# Connectors2.net
KiCad netlist of a schematic drawn in Altium Designer
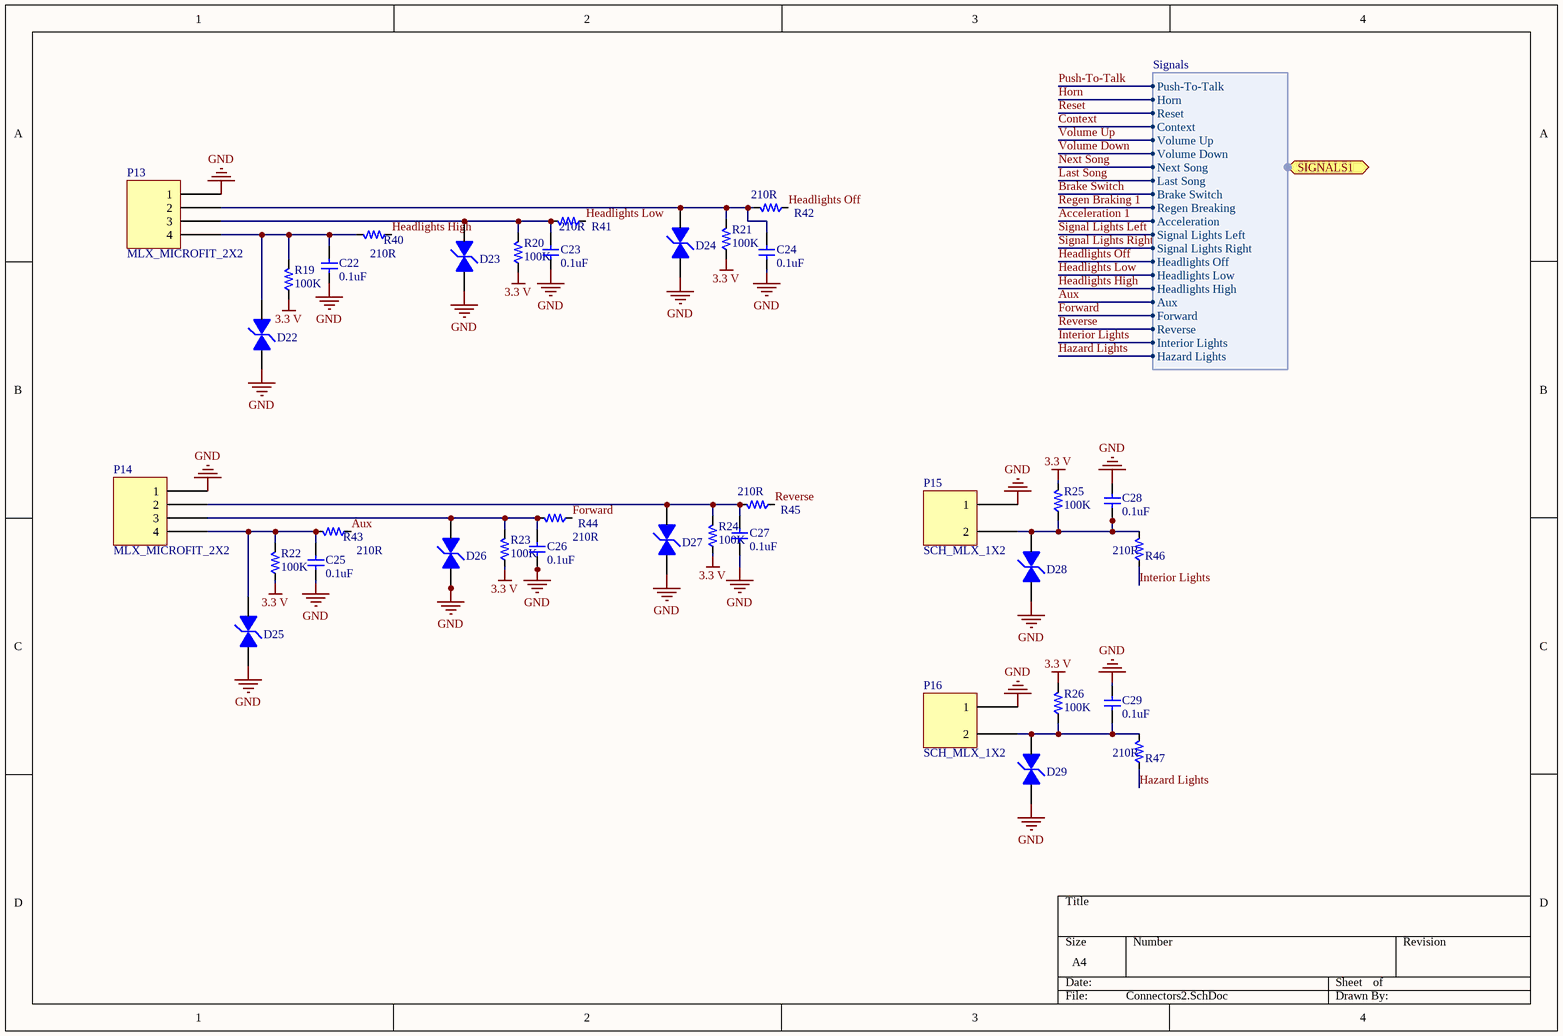
[diagram p0: Connectors2.SchDoc]

(export (version "E")
  (design (tool "Eeschema 10.0.6"))
  (components
    (comp (ref "C22")
      (value "0.1uF")
      (footprint "PCB_GENERIC_SMD_0603")
      (description "CAP CER 0603 0.1uF 16V X5R 20%")
      (fields (field (name "TOLERANCE") "20%") (field (name "VOLTAGE") "16V"))
      (libsource (lib "CAP-0603") (part "C060-000U1-00"))
    )
    (comp (ref "C23")
      (value "0.1uF")
      (footprint "PCB_GENERIC_SMD_0603")
      (description "CAP CER 0603 0.1uF 16V X5R 20%")
      (fields (field (name "TOLERANCE") "20%") (field (name "VOLTAGE") "16V"))
      (libsource (lib "CAP-0603") (part "C060-000U1-00"))
    )
    (comp (ref "C24")
      (value "0.1uF")
      (footprint "PCB_GENERIC_SMD_0603")
      (description "CAP CER 0603 0.1uF 16V X5R 20%")
      (fields (field (name "TOLERANCE") "20%") (field (name "VOLTAGE") "16V"))
      (libsource (lib "CAP-0603") (part "C060-000U1-00"))
    )
    (comp (ref "C25")
      (value "0.1uF")
      (footprint "PCB_GENERIC_SMD_0603")
      (description "CAP CER 0603 0.1uF 16V X5R 20%")
      (fields (field (name "TOLERANCE") "20%") (field (name "VOLTAGE") "16V"))
      (libsource (lib "CAP-0603") (part "C060-000U1-00"))
    )
    (comp (ref "C26")
      (value "0.1uF")
      (footprint "PCB_GENERIC_SMD_0603")
      (description "CAP CER 0603 0.1uF 16V X5R 20%")
      (fields (field (name "TOLERANCE") "20%") (field (name "VOLTAGE") "16V"))
      (libsource (lib "CAP-0603") (part "C060-000U1-00"))
    )
    (comp (ref "C27")
      (value "0.1uF")
      (footprint "PCB_GENERIC_SMD_0603")
      (description "CAP CER 0603 0.1uF 16V X5R 20%")
      (fields (field (name "TOLERANCE") "20%") (field (name "VOLTAGE") "16V"))
      (libsource (lib "CAP-0603") (part "C060-000U1-00"))
    )
    (comp (ref "C28")
      (value "0.1uF")
      (footprint "PCB_GENERIC_SMD_0603")
      (description "CAP CER 0603 0.1uF 16V X5R 20%")
      (fields (field (name "TOLERANCE") "20%") (field (name "VOLTAGE") "16V"))
      (libsource (lib "CAP-0603") (part "C060-000U1-00"))
    )
    (comp (ref "C29")
      (value "0.1uF")
      (footprint "PCB_GENERIC_SMD_0603")
      (description "CAP CER 0603 0.1uF 16V X5R 20%")
      (fields (field (name "TOLERANCE") "20%") (field (name "VOLTAGE") "16V"))
      (libsource (lib "CAP-0603") (part "C060-000U1-00"))
    )
    (comp (ref "D22")
      (value "TVS Diode")
      (footprint "TVS Diode")
      (fields (field (name "MANUFACTURER") "Bourns"))
      (libsource (lib "TVS Diode") (part "TVS Diode"))
    )
    (comp (ref "D23")
      (value "TVS Diode")
      (footprint "TVS Diode")
      (fields (field (name "MANUFACTURER") "Bourns"))
      (libsource (lib "TVS Diode") (part "TVS Diode"))
    )
    (comp (ref "D24")
      (value "TVS Diode")
      (footprint "TVS Diode")
      (fields (field (name "MANUFACTURER") "Bourns"))
      (libsource (lib "TVS Diode") (part "TVS Diode"))
    )
    (comp (ref "D25")
      (value "TVS Diode")
      (footprint "TVS Diode")
      (fields (field (name "MANUFACTURER") "Bourns"))
      (libsource (lib "TVS Diode") (part "TVS Diode"))
    )
    (comp (ref "D26")
      (value "TVS Diode")
      (footprint "TVS Diode")
      (fields (field (name "MANUFACTURER") "Bourns"))
      (libsource (lib "TVS Diode") (part "TVS Diode"))
    )
    (comp (ref "D27")
      (value "TVS Diode")
      (footprint "TVS Diode")
      (fields (field (name "MANUFACTURER") "Bourns"))
      (libsource (lib "TVS Diode") (part "TVS Diode"))
    )
    (comp (ref "D28")
      (value "TVS Diode")
      (footprint "TVS Diode")
      (fields (field (name "MANUFACTURER") "Bourns"))
      (libsource (lib "TVS Diode") (part "TVS Diode"))
    )
    (comp (ref "D29")
      (value "TVS Diode")
      (footprint "TVS Diode")
      (fields (field (name "MANUFACTURER") "Bourns"))
      (libsource (lib "TVS Diode") (part "TVS Diode"))
    )
    (comp (ref "P13")
      (value "MLX_MICROFIT_2X2")
      (footprint "MLX_MICROFIT_2X2")
      (libsource (lib "Molex Microfit 3.0 2x2") (part "MLX_MICROFIT_2X2"))
    )
    (comp (ref "P14")
      (value "MLX_MICROFIT_2X2")
      (footprint "MLX_MICROFIT_2X2")
      (libsource (lib "Molex Microfit 3.0 2x2") (part "MLX_MICROFIT_2X2"))
    )
    (comp (ref "P15")
      (value "SCH_MLX_1X2")
      (footprint "PCB_MLX_MICROFIT_1X2")
      (libsource (lib "Molex Microfit 3.0 1x2") (part "SCH_MLX_1X2"))
    )
    (comp (ref "P16")
      (value "SCH_MLX_1X2")
      (footprint "PCB_MLX_MICROFIT_1X2")
      (libsource (lib "Molex Microfit 3.0 1x2") (part "SCH_MLX_1X2"))
    )
    (comp (ref "R19")
      (value "100K")
      (footprint "PCB_GENERIC_SMD_0603")
      (description "RES 0603 100K 5% 63mW")
      (fields (field (name "TOLERANCE") "5%") (field (name "POWER") "63mW"))
      (libsource (lib "RES-0603") (part "R060-00104-05"))
    )
    (comp (ref "R20")
      (value "100K")
      (footprint "PCB_GENERIC_SMD_0603")
      (description "RES 0603 100K 5% 63mW")
      (fields (field (name "TOLERANCE") "5%") (field (name "POWER") "63mW"))
      (libsource (lib "RES-0603") (part "R060-00104-05"))
    )
    (comp (ref "R21")
      (value "100K")
      (footprint "PCB_GENERIC_SMD_0603")
      (description "RES 0603 100K 5% 63mW")
      (fields (field (name "TOLERANCE") "5%") (field (name "POWER") "63mW"))
      (libsource (lib "RES-0603") (part "R060-00104-05"))
    )
    (comp (ref "R22")
      (value "100K")
      (footprint "PCB_GENERIC_SMD_0603")
      (description "RES 0603 100K 5% 63mW")
      (fields (field (name "TOLERANCE") "5%") (field (name "POWER") "63mW"))
      (libsource (lib "RES-0603") (part "R060-00104-05"))
    )
    (comp (ref "R23")
      (value "100K")
      (footprint "PCB_GENERIC_SMD_0603")
      (description "RES 0603 100K 5% 63mW")
      (fields (field (name "TOLERANCE") "5%") (field (name "POWER") "63mW"))
      (libsource (lib "RES-0603") (part "R060-00104-05"))
    )
    (comp (ref "R24")
      (value "100K")
      (footprint "PCB_GENERIC_SMD_0603")
      (description "RES 0603 100K 5% 63mW")
      (fields (field (name "TOLERANCE") "5%") (field (name "POWER") "63mW"))
      (libsource (lib "RES-0603") (part "R060-00104-05"))
    )
    (comp (ref "R25")
      (value "100K")
      (footprint "PCB_GENERIC_SMD_0603")
      (description "RES 0603 100K 5% 63mW")
      (fields (field (name "TOLERANCE") "5%") (field (name "POWER") "63mW"))
      (libsource (lib "RES-0603") (part "R060-00104-05"))
    )
    (comp (ref "R26")
      (value "100K")
      (footprint "PCB_GENERIC_SMD_0603")
      (description "RES 0603 100K 5% 63mW")
      (fields (field (name "TOLERANCE") "5%") (field (name "POWER") "63mW"))
      (libsource (lib "RES-0603") (part "R060-00104-05"))
    )
    (comp (ref "R40")
      (value "SCH_GENERIC_RESISTOR_0603")
      (footprint "PCB_GENERIC_SMD_0603")
      (description "Generic SMD resistor 0603")
      (fields (field (name "RESISTANCE") "210R"))
      (libsource (lib "Generic 0603 Resistor") (part "SCH_GENERIC_RESISTOR_0603"))
    )
    (comp (ref "R41")
      (value "SCH_GENERIC_RESISTOR_0603")
      (footprint "PCB_GENERIC_SMD_0603")
      (description "Generic SMD resistor 0603")
      (fields (field (name "RESISTANCE") "210R"))
      (libsource (lib "Generic 0603 Resistor") (part "SCH_GENERIC_RESISTOR_0603"))
    )
    (comp (ref "R42")
      (value "SCH_GENERIC_RESISTOR_0603")
      (footprint "PCB_GENERIC_SMD_0603")
      (description "Generic SMD resistor 0603")
      (fields (field (name "RESISTANCE") "210R"))
      (libsource (lib "Generic 0603 Resistor") (part "SCH_GENERIC_RESISTOR_0603"))
    )
    (comp (ref "R43")
      (value "SCH_GENERIC_RESISTOR_0603")
      (footprint "PCB_GENERIC_SMD_0603")
      (description "Generic SMD resistor 0603")
      (fields (field (name "RESISTANCE") "210R"))
      (libsource (lib "Generic 0603 Resistor") (part "SCH_GENERIC_RESISTOR_0603"))
    )
    (comp (ref "R44")
      (value "SCH_GENERIC_RESISTOR_0603")
      (footprint "PCB_GENERIC_SMD_0603")
      (description "Generic SMD resistor 0603")
      (fields (field (name "RESISTANCE") "210R"))
      (libsource (lib "Generic 0603 Resistor") (part "SCH_GENERIC_RESISTOR_0603"))
    )
    (comp (ref "R45")
      (value "SCH_GENERIC_RESISTOR_0603")
      (footprint "PCB_GENERIC_SMD_0603")
      (description "Generic SMD resistor 0603")
      (fields (field (name "RESISTANCE") "210R"))
      (libsource (lib "Generic 0603 Resistor") (part "SCH_GENERIC_RESISTOR_0603"))
    )
    (comp (ref "R46")
      (value "SCH_GENERIC_RESISTOR_0603")
      (footprint "PCB_GENERIC_SMD_0603")
      (description "Generic SMD resistor 0603")
      (fields (field (name "RESISTANCE") "210R"))
      (libsource (lib "Generic 0603 Resistor") (part "SCH_GENERIC_RESISTOR_0603"))
    )
    (comp (ref "R47")
      (value "SCH_GENERIC_RESISTOR_0603")
      (footprint "PCB_GENERIC_SMD_0603")
      (description "Generic SMD resistor 0603")
      (fields (field (name "RESISTANCE") "210R"))
      (libsource (lib "Generic 0603 Resistor") (part "SCH_GENERIC_RESISTOR_0603"))
    )
  )
  (nets
    (net (code "3") (name "/Aux") (class "Default")
      (node (ref "R43") (pin "1") (pinfunction "1_1") (pintype "passive"))
    )
    (net (code "6") (name "/Forward") (class "Default")
      (node (ref "R44") (pin "1") (pinfunction "1_1") (pintype "passive"))
    )
    (net (code "7") (name "/Hazard Lights") (class "Default")
      (node (ref "R47") (pin "1") (pinfunction "1_1") (pintype "passive"))
    )
    (net (code "8") (name "/Headlights High") (class "Default")
      (node (ref "R40") (pin "1") (pinfunction "1_1") (pintype "passive"))
    )
    (net (code "9") (name "/Headlights Low") (class "Default")
      (node (ref "R41") (pin "1") (pinfunction "1_1") (pintype "passive"))
    )
    (net (code "10") (name "/Headlights Off") (class "Default")
      (node (ref "R42") (pin "1") (pinfunction "1_1") (pintype "passive"))
    )
    (net (code "12") (name "/Interior Lights") (class "Default")
      (node (ref "R46") (pin "1") (pinfunction "1_1") (pintype "passive"))
    )
    (net (code "18") (name "/Reverse") (class "Default")
      (node (ref "R45") (pin "1") (pinfunction "1_1") (pintype "passive"))
    )
    (net (code "24") (name "3.3 V") (class "Default")
      (node (ref "R22") (pin "1") (pinfunction "1_1") (pintype "passive"))
      (node (ref "R23") (pin "1") (pinfunction "1_1") (pintype "passive"))
      (node (ref "R24") (pin "1") (pinfunction "1_1") (pintype "passive"))
      (node (ref "R25") (pin "2") (pinfunction "2_2") (pintype "passive"))
    )
    (net (code "25") (name "GND") (class "Default")
      (node (ref "C24") (pin "1") (pinfunction "1_1") (pintype "passive"))
      (node (ref "C25") (pin "1") (pinfunction "1_1") (pintype "passive"))
      (node (ref "C26") (pin "1") (pinfunction "1_1") (pintype "passive"))
      (node (ref "C27") (pin "1") (pinfunction "1_1") (pintype "passive"))
      (node (ref "C29") (pin "2") (pinfunction "2_2") (pintype "passive"))
      (node (ref "D22") (pin "2") (pintype "passive"))
      (node (ref "D23") (pin "2") (pintype "passive"))
      (node (ref "D24") (pin "2") (pintype "passive"))
      (node (ref "D25") (pin "2") (pintype "passive"))
      (node (ref "D26") (pin "2") (pintype "passive"))
      (node (ref "D27") (pin "2") (pintype "passive"))
      (node (ref "D28") (pin "2") (pintype "passive"))
      (node (ref "D29") (pin "2") (pintype "passive"))
      (node (ref "P13") (pin "1") (pinfunction "1_1") (pintype "passive"))
      (node (ref "P14") (pin "1") (pinfunction "1_1") (pintype "passive"))
      (node (ref "P15") (pin "1") (pinfunction "1_1") (pintype "passive"))
      (node (ref "P16") (pin "1") (pinfunction "1_1") (pintype "passive"))
    )
    (net (code "26") (name "Net-(C22-Pad2)") (class "Default")
      (node (ref "C22") (pin "2") (pinfunction "2_2") (pintype "passive"))
      (node (ref "D22") (pin "1") (pintype "passive"))
      (node (ref "P13") (pin "4") (pinfunction "4_4") (pintype "passive"))
      (node (ref "R19") (pin "2") (pinfunction "2_2") (pintype "passive"))
      (node (ref "R40") (pin "2") (pinfunction "2_2") (pintype "passive"))
    )
    (net (code "27") (name "Net-(C23-Pad2)") (class "Default")
      (node (ref "C23") (pin "2") (pinfunction "2_2") (pintype "passive"))
      (node (ref "D23") (pin "1") (pintype "passive"))
      (node (ref "P13") (pin "3") (pinfunction "3_3") (pintype "passive"))
      (node (ref "R20") (pin "2") (pinfunction "2_2") (pintype "passive"))
      (node (ref "R41") (pin "2") (pinfunction "2_2") (pintype "passive"))
    )
    (net (code "28") (name "Net-(C24-Pad2)") (class "Default")
      (node (ref "C24") (pin "2") (pinfunction "2_2") (pintype "passive"))
      (node (ref "D24") (pin "1") (pintype "passive"))
      (node (ref "P13") (pin "2") (pinfunction "2_2") (pintype "passive"))
      (node (ref "R21") (pin "2") (pinfunction "2_2") (pintype "passive"))
      (node (ref "R42") (pin "2") (pinfunction "2_2") (pintype "passive"))
    )
    (net (code "29") (name "Net-(C25-Pad2)") (class "Default")
      (node (ref "C25") (pin "2") (pinfunction "2_2") (pintype "passive"))
      (node (ref "D25") (pin "1") (pintype "passive"))
      (node (ref "P14") (pin "4") (pinfunction "4_4") (pintype "passive"))
      (node (ref "R22") (pin "2") (pinfunction "2_2") (pintype "passive"))
      (node (ref "R43") (pin "2") (pinfunction "2_2") (pintype "passive"))
    )
    (net (code "30") (name "Net-(C26-Pad2)") (class "Default")
      (node (ref "C26") (pin "2") (pinfunction "2_2") (pintype "passive"))
      (node (ref "D26") (pin "1") (pintype "passive"))
      (node (ref "P14") (pin "3") (pinfunction "3_3") (pintype "passive"))
      (node (ref "R23") (pin "2") (pinfunction "2_2") (pintype "passive"))
      (node (ref "R44") (pin "2") (pinfunction "2_2") (pintype "passive"))
    )
    (net (code "31") (name "Net-(C27-Pad2)") (class "Default")
      (node (ref "C27") (pin "2") (pinfunction "2_2") (pintype "passive"))
      (node (ref "D27") (pin "1") (pintype "passive"))
      (node (ref "P14") (pin "2") (pinfunction "2_2") (pintype "passive"))
      (node (ref "R24") (pin "2") (pinfunction "2_2") (pintype "passive"))
      (node (ref "R45") (pin "2") (pinfunction "2_2") (pintype "passive"))
    )
    (net (code "32") (name "Net-(C28-Pad1)") (class "Default")
      (node (ref "C28") (pin "1") (pinfunction "1_1") (pintype "passive"))
      (node (ref "D28") (pin "1") (pintype "passive"))
      (node (ref "P15") (pin "2") (pinfunction "2_2") (pintype "passive"))
      (node (ref "R25") (pin "1") (pinfunction "1_1") (pintype "passive"))
      (node (ref "R46") (pin "2") (pinfunction "2_2") (pintype "passive"))
    )
    (net (code "33") (name "Net-(C29-Pad1)") (class "Default")
      (node (ref "C29") (pin "1") (pinfunction "1_1") (pintype "passive"))
      (node (ref "D29") (pin "1") (pintype "passive"))
      (node (ref "P16") (pin "2") (pinfunction "2_2") (pintype "passive"))
      (node (ref "R26") (pin "1") (pinfunction "1_1") (pintype "passive"))
      (node (ref "R47") (pin "2") (pinfunction "2_2") (pintype "passive"))
    )
    (net (code "34") (name "unconnected-(C22-Pad1)") (class "Default")
      (node (ref "C22") (pin "1") (pinfunction "1_1") (pintype "passive"))
    )
    (net (code "35") (name "unconnected-(C23-Pad1)") (class "Default")
      (node (ref "C23") (pin "1") (pinfunction "1_1") (pintype "passive"))
    )
    (net (code "36") (name "unconnected-(C28-Pad2)") (class "Default")
      (node (ref "C28") (pin "2") (pinfunction "2_2") (pintype "passive"))
    )
    (net (code "37") (name "unconnected-(R19-Pad1)") (class "Default")
      (node (ref "R19") (pin "1") (pinfunction "1_1") (pintype "passive"))
    )
    (net (code "38") (name "unconnected-(R20-Pad1)") (class "Default")
      (node (ref "R20") (pin "1") (pinfunction "1_1") (pintype "passive"))
    )
    (net (code "39") (name "unconnected-(R21-Pad1)") (class "Default")
      (node (ref "R21") (pin "1") (pinfunction "1_1") (pintype "passive"))
    )
    (net (code "40") (name "unconnected-(R26-Pad2)") (class "Default")
      (node (ref "R26") (pin "2") (pinfunction "2_2") (pintype "passive"))
    )
  )
)
